# npt_client_wifi_board.net
KiCad netlist of a schematic drawn in Altium Designer
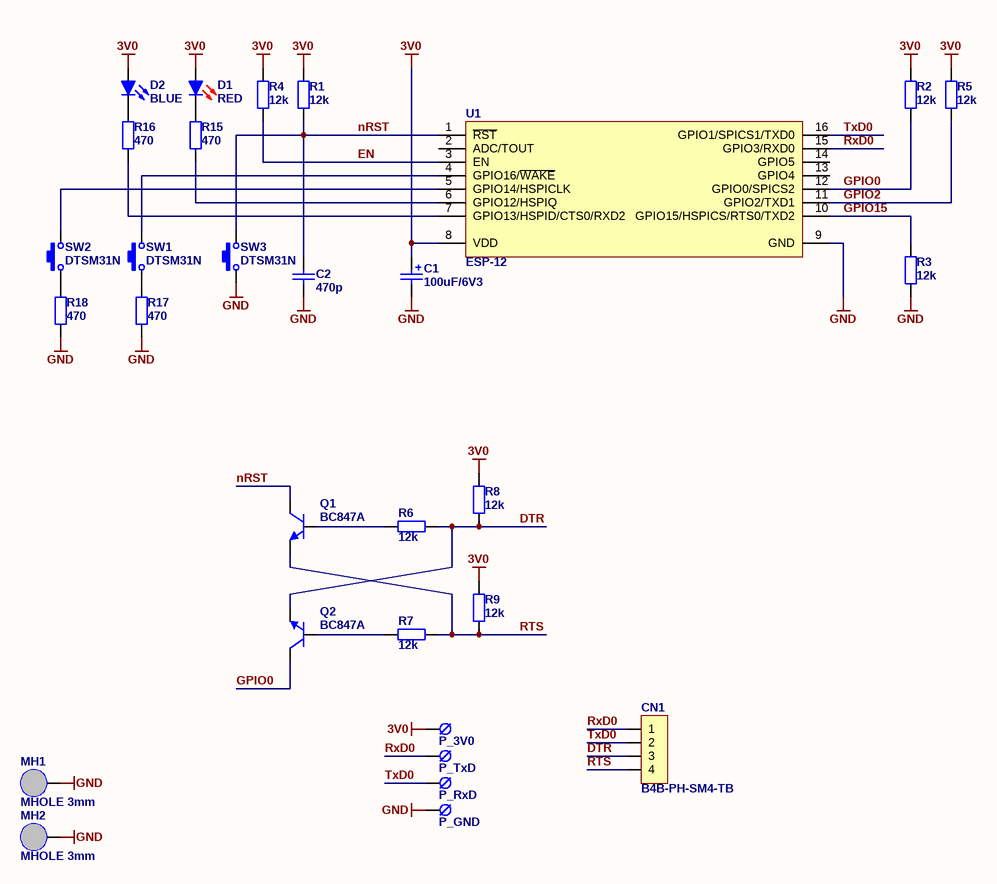
[diagram p0: npt_client_wifi_board.SchDoc]

(export (version "E")
  (design (tool "Eeschema 10.0.6"))
  (components
    (comp (ref "C1")
      (value "100uF/6V3")
      (footprint "SMDB")
      (description "Polarized Tantalum Capacitor")
      (libsource (lib "capacitors") (part "Cap Pol Tant"))
    )
    (comp (ref "C2")
      (value "470p")
      (footprint "C0805")
      (description "Capacitor")
      (libsource (lib "capacitors") (part "Cap"))
    )
    (comp (ref "CN1")
      (value "B4B-PH-SM4-TB")
      (footprint "B4B-PH-SM4-TB")
      (libsource (lib "jst") (part "B4B-PH-SM4-TB"))
    )
    (comp (ref "D1")
      (value "RED")
      (footprint "LED0805R")
      (description "RED LED")
      (libsource (lib "leds") (part "LED_RED"))
    )
    (comp (ref "D2")
      (value "BLUE")
      (footprint "LED0805B")
      (description "BLUE LED")
      (libsource (lib "leds") (part "LED_BLUE"))
    )
    (comp (ref "MH1")
      (value "MHOLE 3mm")
      (footprint "3mm screw drill I")
      (description "3mm Mounting Hole")
      (libsource (lib "mechanical_other") (part "MHOLE_3MM"))
    )
    (comp (ref "MH2")
      (value "MHOLE 3mm")
      (footprint "3mm screw drill I")
      (description "3mm Mounting Hole")
      (libsource (lib "mechanical_other") (part "MHOLE_3MM"))
    )
    (comp (ref "P_3V0")
      (value "CablePAD")
      (footprint "PADSMD2x3mm")
      (description "Cable PAD")
      (libsource (lib "others") (part "CablePAD"))
    )
    (comp (ref "P_GND")
      (value "CablePAD")
      (footprint "PADSMD2x3mm")
      (description "Cable PAD")
      (libsource (lib "others") (part "CablePAD"))
    )
    (comp (ref "P_RxD")
      (value "CablePAD")
      (footprint "PADSMD2x3mm")
      (description "Cable PAD")
      (libsource (lib "others") (part "CablePAD"))
    )
    (comp (ref "P_TxD")
      (value "CablePAD")
      (footprint "PADSMD2x3mm")
      (description "Cable PAD")
      (libsource (lib "others") (part "CablePAD"))
    )
    (comp (ref "Q1")
      (value "BC847A")
      (footprint "SOT-23")
      (description "NPN General Purpose Transistor (VCE=45V, IC=100mA, HFE=110-220)")
      (libsource (lib "transistors_bjt") (part "BC847A"))
    )
    (comp (ref "Q2")
      (value "BC847A")
      (footprint "SOT-23")
      (description "NPN General Purpose Transistor (VCE=45V, IC=100mA, HFE=110-220)")
      (libsource (lib "transistors_bjt") (part "BC847A"))
    )
    (comp (ref "R1")
      (value "12k")
      (footprint "R0805")
      (description "Resistor")
      (libsource (lib "resistors") (part "Res"))
    )
    (comp (ref "R2")
      (value "12k")
      (footprint "R0805")
      (description "Resistor")
      (libsource (lib "resistors") (part "Res"))
    )
    (comp (ref "R3")
      (value "12k")
      (footprint "R0805")
      (description "Resistor")
      (libsource (lib "resistors") (part "Res"))
    )
    (comp (ref "R4")
      (value "12k")
      (footprint "R0805")
      (description "Resistor")
      (libsource (lib "resistors") (part "Res"))
    )
    (comp (ref "R5")
      (value "12k")
      (footprint "R0805")
      (description "Resistor")
      (libsource (lib "resistors") (part "Res"))
    )
    (comp (ref "R6")
      (value "12k")
      (footprint "R0805")
      (description "Resistor")
      (libsource (lib "") (part "Res_2"))
    )
    (comp (ref "R7")
      (value "12k")
      (footprint "R0805")
      (description "Resistor")
      (libsource (lib "") (part "Res_2"))
    )
    (comp (ref "R8")
      (value "12k")
      (footprint "R0805")
      (description "Resistor")
      (libsource (lib "") (part "Res_1"))
    )
    (comp (ref "R9")
      (value "12k")
      (footprint "R0805")
      (description "Resistor")
      (libsource (lib "") (part "Res_1"))
    )
    (comp (ref "R15")
      (value "470")
      (footprint "R0805")
      (description "Resistor")
      (libsource (lib "resistors") (part "Res"))
    )
    (comp (ref "R16")
      (value "470")
      (footprint "R0805")
      (description "Resistor")
      (libsource (lib "resistors") (part "Res"))
    )
    (comp (ref "R17")
      (value "470")
      (footprint "R0805")
      (description "Resistor")
      (libsource (lib "resistors") (part "Res"))
    )
    (comp (ref "R18")
      (value "470")
      (footprint "R0805")
      (description "Resistor")
      (libsource (lib "resistors") (part "Res"))
    )
    (comp (ref "SW1")
      (value "DTSM31N")
      (footprint "DTSM-3")
      (description "DIPTRONICS 6x3,5mm SMD Tactile SPST-NO Switch")
      (libsource (lib "microswitches") (part "DTSM31N"))
    )
    (comp (ref "SW2")
      (value "DTSM31N")
      (footprint "DTSM-3")
      (description "DIPTRONICS 6x3,5mm SMD Tactile SPST-NO Switch")
      (libsource (lib "microswitches") (part "DTSM31N"))
    )
    (comp (ref "SW3")
      (value "DTSM31N")
      (footprint "DTSM-3")
      (description "DIPTRONICS 6x3,5mm SMD Tactile SPST-NO Switch")
      (libsource (lib "microswitches") (part "DTSM31N"))
    )
    (comp (ref "U1")
      (value "ESP-12")
      (footprint "ESP-12")
      (description "ESP-12 Wi-Fi Module by AI-Thinker")
      (libsource (lib "wireless_modules") (part "ESP-12"))
    )
  )
  (nets
    (net (code "1") (name "/DTR") (class "Default")
      (node (ref "CN1") (pin "3") (pinfunction "3_3") (pintype "passive"))
      (node (ref "Q2") (pin "2") (pinfunction "E_2") (pintype "passive"))
      (node (ref "R6") (pin "1") (pinfunction "1_1") (pintype "passive"))
      (node (ref "R8") (pin "1") (pinfunction "1_1") (pintype "passive"))
    )
    (net (code "2") (name "/EN") (class "Default")
      (node (ref "R4") (pin "2") (pinfunction "2_2") (pintype "passive"))
      (node (ref "U1") (pin "3") (pinfunction "EN_3") (pintype "passive"))
    )
    (net (code "3") (name "/GPIO0") (class "Default")
      (node (ref "Q2") (pin "3") (pinfunction "C_3") (pintype "passive"))
      (node (ref "R2") (pin "2") (pinfunction "2_2") (pintype "passive"))
      (node (ref "U1") (pin "12") (pinfunction "GPIO0/SPICS2_12") (pintype "passive"))
    )
    (net (code "4") (name "/GPIO2") (class "Default")
      (node (ref "R5") (pin "2") (pinfunction "2_2") (pintype "passive"))
      (node (ref "U1") (pin "11") (pinfunction "GPIO2/TXD1_11") (pintype "passive"))
    )
    (net (code "5") (name "/GPIO15") (class "Default")
      (node (ref "R3") (pin "1") (pinfunction "1_1") (pintype "passive"))
      (node (ref "U1") (pin "10") (pinfunction "GPIO15/HSPICS/RTS0/TXD2_10") (pintype "passive"))
    )
    (net (code "6") (name "/RTS") (class "Default")
      (node (ref "CN1") (pin "4") (pinfunction "4_4") (pintype "passive"))
      (node (ref "Q1") (pin "2") (pinfunction "E_2") (pintype "passive"))
      (node (ref "R7") (pin "1") (pinfunction "1_1") (pintype "passive"))
      (node (ref "R9") (pin "1") (pinfunction "1_1") (pintype "passive"))
    )
    (net (code "7") (name "/RxD0") (class "Default")
      (node (ref "CN1") (pin "1") (pinfunction "1_1") (pintype "passive"))
      (node (ref "P_TxD") (pin "0") (pinfunction "0_0") (pintype "passive"))
      (node (ref "U1") (pin "15") (pinfunction "GPIO3/RXD0_15") (pintype "passive"))
    )
    (net (code "8") (name "/TxD0") (class "Default")
      (node (ref "CN1") (pin "2") (pinfunction "2_2") (pintype "passive"))
      (node (ref "P_RxD") (pin "0") (pinfunction "0_0") (pintype "passive"))
      (node (ref "U1") (pin "16") (pinfunction "GPIO1/SPICS1/TXD0_16") (pintype "passive"))
    )
    (net (code "9") (name "/nRST") (class "Default")
      (node (ref "C2") (pin "2") (pinfunction "2_2") (pintype "passive"))
      (node (ref "Q1") (pin "3") (pinfunction "C_3") (pintype "passive"))
      (node (ref "R1") (pin "2") (pinfunction "2_2") (pintype "passive"))
      (node (ref "SW3") (pin "2") (pinfunction "2_2") (pintype "passive"))
      (node (ref "U1") (pin "1") (pinfunction "~{RST}_1") (pintype "passive"))
    )
    (net (code "10") (name "3V0") (class "Default")
      (node (ref "C1") (pin "1") (pinfunction "1_1") (pintype "passive"))
      (node (ref "D1") (pin "1") (pinfunction "A_1") (pintype "passive"))
      (node (ref "D2") (pin "1") (pinfunction "A_1") (pintype "passive"))
      (node (ref "P_3V0") (pin "0") (pinfunction "0_0") (pintype "passive"))
      (node (ref "R1") (pin "1") (pinfunction "1_1") (pintype "passive"))
      (node (ref "R2") (pin "1") (pinfunction "1_1") (pintype "passive"))
      (node (ref "R4") (pin "1") (pinfunction "1_1") (pintype "passive"))
      (node (ref "R5") (pin "1") (pinfunction "1_1") (pintype "passive"))
      (node (ref "R8") (pin "2") (pinfunction "2_2") (pintype "passive"))
      (node (ref "R9") (pin "2") (pinfunction "2_2") (pintype "passive"))
      (node (ref "U1") (pin "8") (pinfunction "VDD_8") (pintype "passive"))
    )
    (net (code "11") (name "GND") (class "Default")
      (node (ref "C1") (pin "2") (pinfunction "2_2") (pintype "passive"))
      (node (ref "C2") (pin "1") (pinfunction "1_1") (pintype "passive"))
      (node (ref "MH1") (pin "1") (pinfunction "GND_1") (pintype "passive"))
      (node (ref "MH2") (pin "1") (pinfunction "GND_1") (pintype "passive"))
      (node (ref "P_GND") (pin "0") (pinfunction "0_0") (pintype "passive"))
      (node (ref "R17") (pin "2") (pinfunction "2_2") (pintype "passive"))
      (node (ref "R18") (pin "2") (pinfunction "2_2") (pintype "passive"))
      (node (ref "R3") (pin "2") (pinfunction "2_2") (pintype "passive"))
      (node (ref "SW3") (pin "1") (pinfunction "1_1") (pintype "passive"))
      (node (ref "U1") (pin "9") (pinfunction "GND_9") (pintype "passive"))
    )
    (net (code "12") (name "Net-(D1-K)") (class "Default")
      (node (ref "D1") (pin "2") (pinfunction "K_2") (pintype "passive"))
      (node (ref "R15") (pin "1") (pinfunction "1_1") (pintype "passive"))
    )
    (net (code "13") (name "Net-(D2-K)") (class "Default")
      (node (ref "D2") (pin "2") (pinfunction "K_2") (pintype "passive"))
      (node (ref "R16") (pin "1") (pinfunction "1_1") (pintype "passive"))
    )
    (net (code "14") (name "Net-(Q1-B)") (class "Default")
      (node (ref "Q1") (pin "1") (pinfunction "B_1") (pintype "passive"))
      (node (ref "R6") (pin "2") (pinfunction "2_2") (pintype "passive"))
    )
    (net (code "15") (name "Net-(Q2-B)") (class "Default")
      (node (ref "Q2") (pin "1") (pinfunction "B_1") (pintype "passive"))
      (node (ref "R7") (pin "2") (pinfunction "2_2") (pintype "passive"))
    )
    (net (code "16") (name "Net-(R17-Pad1)") (class "Default")
      (node (ref "R17") (pin "1") (pinfunction "1_1") (pintype "passive"))
      (node (ref "SW1") (pin "1") (pinfunction "1_1") (pintype "passive"))
    )
    (net (code "17") (name "Net-(R18-Pad1)") (class "Default")
      (node (ref "R18") (pin "1") (pinfunction "1_1") (pintype "passive"))
      (node (ref "SW2") (pin "1") (pinfunction "1_1") (pintype "passive"))
    )
    (net (code "18") (name "Net-(U1-GPIO12{slash}HSPIQ)") (class "Default")
      (node (ref "R15") (pin "2") (pinfunction "2_2") (pintype "passive"))
      (node (ref "U1") (pin "6") (pinfunction "GPIO12/HSPIQ_6") (pintype "passive"))
    )
    (net (code "19") (name "Net-(U1-GPIO13{slash}HSPID{slash}CTS0{slash}RXD2)") (class "Default")
      (node (ref "R16") (pin "2") (pinfunction "2_2") (pintype "passive"))
      (node (ref "U1") (pin "7") (pinfunction "GPIO13/HSPID/CTS0/RXD2_7") (pintype "passive"))
    )
    (net (code "20") (name "Net-(U1-GPIO14{slash}HSPICLK)") (class "Default")
      (node (ref "SW2") (pin "2") (pinfunction "2_2") (pintype "passive"))
      (node (ref "U1") (pin "5") (pinfunction "GPIO14/HSPICLK_5") (pintype "passive"))
    )
    (net (code "21") (name "Net-(U1-GPIO16{slash}~{WAKE})") (class "Default")
      (node (ref "SW1") (pin "2") (pinfunction "2_2") (pintype "passive"))
      (node (ref "U1") (pin "4") (pinfunction "GPIO16/~{WAKE}_4") (pintype "passive"))
    )
    (net (code "22") (name "unconnected-(U1-ADC{slash}TOUT-Pad2)") (class "Default")
      (node (ref "U1") (pin "2") (pinfunction "ADC/TOUT_2") (pintype "passive"))
    )
    (net (code "23") (name "unconnected-(U1-GPIO4-Pad13)") (class "Default")
      (node (ref "U1") (pin "13") (pinfunction "GPIO4_13") (pintype "passive"))
    )
    (net (code "24") (name "unconnected-(U1-GPIO5-Pad14)") (class "Default")
      (node (ref "U1") (pin "14") (pinfunction "GPIO5_14") (pintype "passive"))
    )
  )
)
